# WQMS.net
KiCad netlist of a schematic drawn in EAGLE
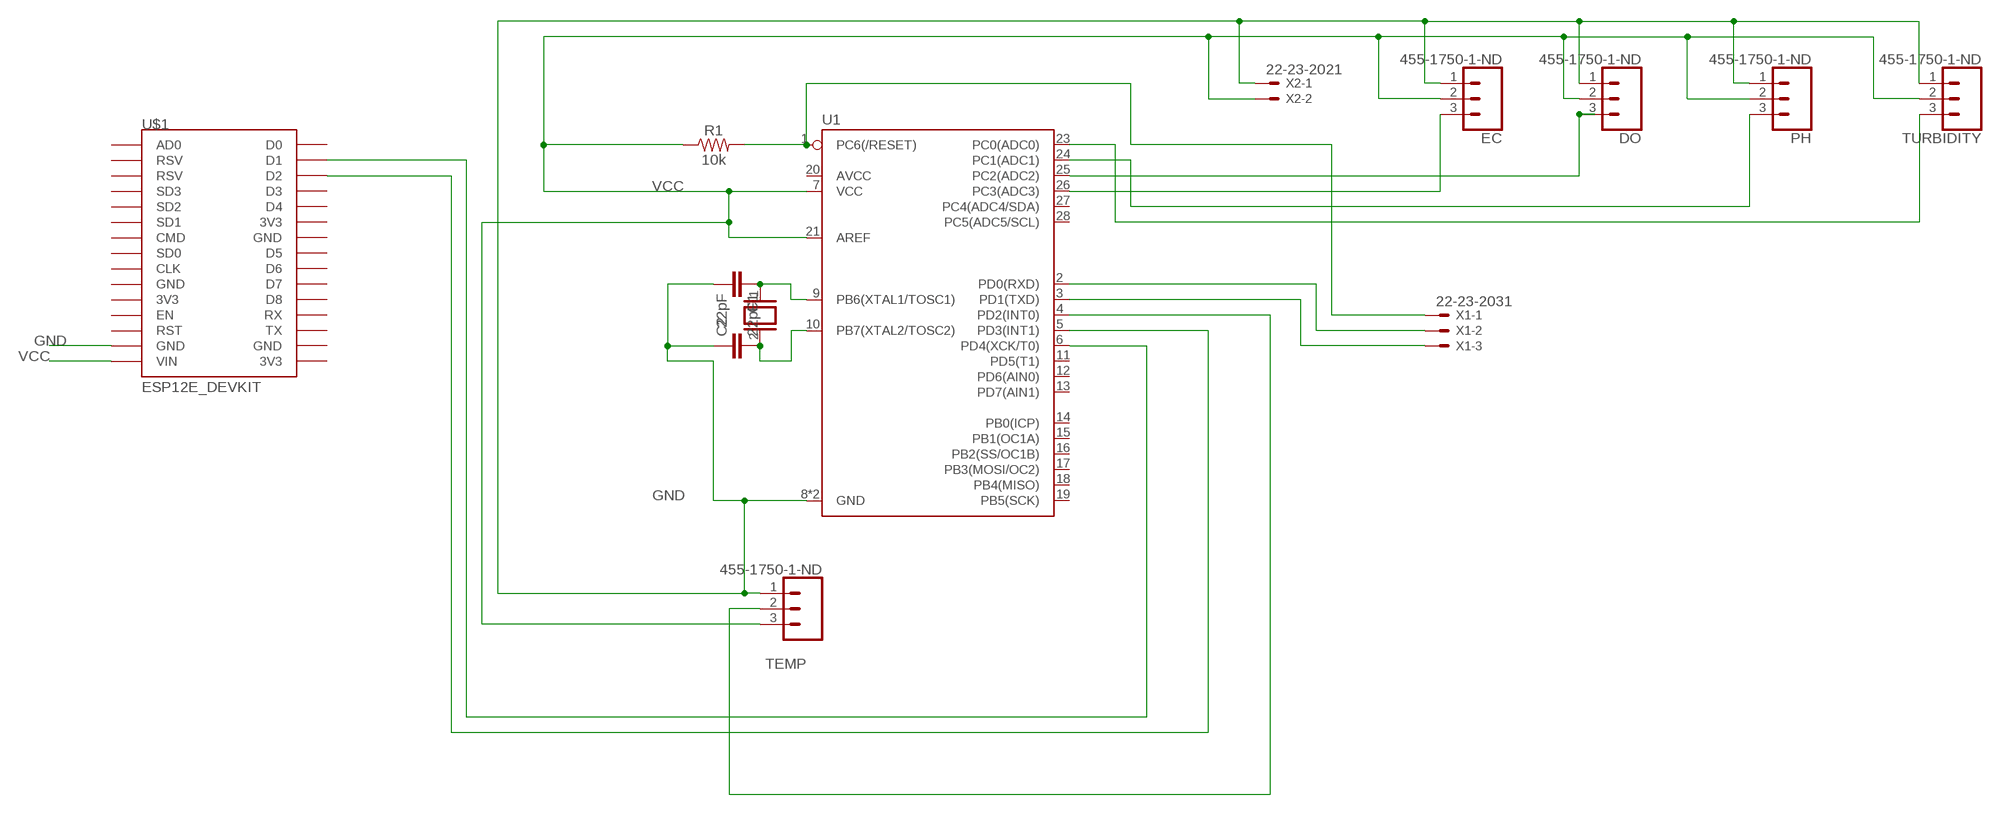
[diagram p0: schematic, sheet 1]

(export (version "E")
  (design (tool "Eeschema 10.0.6"))
  (components
    (comp (ref "C1")
      (value "22pF")
      (footprint "eagle-import:CAP-PTH-2.54")
      (libsource (lib "eagle-import") (part "22PF-PTH-2.54MM-200V-5%"))
    )
    (comp (ref "C2")
      (value "22pF")
      (footprint "eagle-import:CAP-PTH-2.54")
      (libsource (lib "eagle-import") (part "22PF-PTH-2.54MM-200V-5%"))
    )
    (comp (ref "DO")
      (value "455-1750-1-ND")
      (footprint "eagle-import:1X03")
      (libsource (lib "eagle-import") (part "CONN_03"))
    )
    (comp (ref "EC")
      (value "455-1750-1-ND")
      (footprint "eagle-import:1X03")
      (libsource (lib "eagle-import") (part "CONN_03"))
    )
    (comp (ref "PH")
      (value "455-1750-1-ND")
      (footprint "eagle-import:1X03")
      (libsource (lib "eagle-import") (part "CONN_03"))
    )
    (comp (ref "Q1")
      (value "XTAL")
      (footprint "eagle-import:Q")
      (libsource (lib "eagle-import") (part "XTAL"))
    )
    (comp (ref "R1")
      (value "10k")
      (footprint "eagle-import:AXIAL-0.3")
      (libsource (lib "eagle-import") (part "10KOHM-HORIZ-1/4W-1%"))
    )
    (comp (ref "TEMP")
      (value "455-1750-1-ND")
      (footprint "eagle-import:1X03")
      (libsource (lib "eagle-import") (part "CONN_03"))
    )
    (comp (ref "TURBIDITY")
      (value "455-1750-1-ND")
      (footprint "eagle-import:1X03")
      (libsource (lib "eagle-import") (part "CONN_03"))
    )
    (comp (ref "U$1")
      (value "ESP12E_DEVKIT")
      (footprint "eagle-import:ESP12E_DEVKIT")
      (libsource (lib "eagle-import") (part "ESP12E_DEVKIT"))
    )
    (comp (ref "U1")
      (value "328P")
      (footprint "eagle-import:DIP28")
      (libsource (lib "eagle-import") (part "ATMEGA328P_PDIP"))
    )
    (comp (ref "X1")
      (value "22-23-2031")
      (footprint "eagle-import:22-23-2031")
      (fields (field (name "MF") "MOLEX"))
      (libsource (lib "eagle-import") (part "22-23-2031"))
    )
    (comp (ref "X2")
      (value "22-23-2021")
      (footprint "eagle-import:22-23-2021")
      (fields (field (name "MF") "MOLEX"))
      (libsource (lib "eagle-import") (part "22-23-2021"))
    )
  )
  (nets
    (net (code "1") (name "/GND") (class "Default")
      (node (ref "C1") (pin "2") (pinfunction "2_2") (pintype "passive"))
      (node (ref "C2") (pin "1") (pinfunction "1_1") (pintype "passive"))
      (node (ref "DO") (pin "1") (pinfunction "1_1") (pintype "passive"))
      (node (ref "EC") (pin "1") (pinfunction "1_1") (pintype "passive"))
      (node (ref "PH") (pin "1") (pinfunction "1_1") (pintype "passive"))
      (node (ref "TEMP") (pin "1") (pinfunction "1_1") (pintype "passive"))
      (node (ref "TURBIDITY") (pin "1") (pinfunction "1_1") (pintype "passive"))
      (node (ref "U$1") (pin "GND@1") (pinfunction "GND_GND@1") (pintype "bidirectional"))
      (node (ref "U1") (pin "22") (pinfunction "GND_22") (pintype "bidirectional"))
      (node (ref "U1") (pin "8") (pinfunction "GND_8") (pintype "bidirectional"))
      (node (ref "X2") (pin "1") (pinfunction "S_1") (pintype "passive"))
    )
    (net (code "2") (name "/VCC") (class "Default")
      (node (ref "DO") (pin "2") (pinfunction "2_2") (pintype "passive"))
      (node (ref "EC") (pin "2") (pinfunction "2_2") (pintype "passive"))
      (node (ref "PH") (pin "2") (pinfunction "2_2") (pintype "passive"))
      (node (ref "R1") (pin "P$1") (pinfunction "1_P$1") (pintype "passive"))
      (node (ref "R1") (pin "P$2") (pinfunction "2_P$2") (pintype "passive"))
      (node (ref "TEMP") (pin "3") (pinfunction "3_3") (pintype "passive"))
      (node (ref "TURBIDITY") (pin "2") (pinfunction "2_2") (pintype "passive"))
      (node (ref "U$1") (pin "VIN") (pinfunction "VIN_VIN") (pintype "bidirectional"))
      (node (ref "U1") (pin "1") (pinfunction "PC6(/RESET)_1") (pintype "bidirectional"))
      (node (ref "U1") (pin "21") (pinfunction "AREF_21") (pintype "bidirectional"))
      (node (ref "U1") (pin "7") (pinfunction "VCC_7") (pintype "bidirectional"))
      (node (ref "X1") (pin "1") (pinfunction "S_1") (pintype "passive"))
      (node (ref "X2") (pin "2") (pinfunction "S_2") (pintype "passive"))
    )
    (net (code "3") (name "Net-(U1-PB6(XTAL1{slash}TOSC1))") (class "Default")
      (node (ref "C1") (pin "1") (pinfunction "1_1") (pintype "passive"))
      (node (ref "Q1") (pin "1") (pinfunction "1_1") (pintype "passive"))
      (node (ref "U1") (pin "9") (pinfunction "PB6(XTAL1/TOSC1)_9") (pintype "bidirectional"))
    )
    (net (code "4") (name "Net-(U1-PB7(XTAL2{slash}TOSC2))") (class "Default")
      (node (ref "C2") (pin "2") (pinfunction "2_2") (pintype "passive"))
      (node (ref "Q1") (pin "2") (pinfunction "2_2") (pintype "passive"))
      (node (ref "U1") (pin "10") (pinfunction "PB7(XTAL2/TOSC2)_10") (pintype "bidirectional"))
    )
    (net (code "5") (name "Net-(U1-PC0(ADC0))") (class "Default")
      (node (ref "TURBIDITY") (pin "3") (pinfunction "3_3") (pintype "passive"))
      (node (ref "U1") (pin "23") (pinfunction "PC0(ADC0)_23") (pintype "bidirectional"))
    )
    (net (code "6") (name "Net-(U1-PC1(ADC1))") (class "Default")
      (node (ref "PH") (pin "3") (pinfunction "3_3") (pintype "passive"))
      (node (ref "U1") (pin "24") (pinfunction "PC1(ADC1)_24") (pintype "bidirectional"))
    )
    (net (code "7") (name "Net-(U1-PC2(ADC2))") (class "Default")
      (node (ref "DO") (pin "3") (pinfunction "3_3") (pintype "passive"))
      (node (ref "U1") (pin "25") (pinfunction "PC2(ADC2)_25") (pintype "bidirectional"))
    )
    (net (code "8") (name "Net-(U1-PC3(ADC3))") (class "Default")
      (node (ref "EC") (pin "3") (pinfunction "3_3") (pintype "passive"))
      (node (ref "U1") (pin "26") (pinfunction "PC3(ADC3)_26") (pintype "bidirectional"))
    )
    (net (code "9") (name "Net-(U1-PD0(RXD))") (class "Default")
      (node (ref "U1") (pin "2") (pinfunction "PD0(RXD)_2") (pintype "bidirectional"))
      (node (ref "X1") (pin "2") (pinfunction "S_2") (pintype "passive"))
    )
    (net (code "10") (name "Net-(U1-PD1(TXD))") (class "Default")
      (node (ref "U1") (pin "3") (pinfunction "PD1(TXD)_3") (pintype "bidirectional"))
      (node (ref "X1") (pin "3") (pinfunction "S_3") (pintype "passive"))
    )
    (net (code "11") (name "Net-(U1-PD2(INT0))") (class "Default")
      (node (ref "TEMP") (pin "2") (pinfunction "2_2") (pintype "passive"))
      (node (ref "U1") (pin "4") (pinfunction "PD2(INT0)_4") (pintype "bidirectional"))
    )
    (net (code "12") (name "Net-(U1-PD3(INT1))") (class "Default")
      (node (ref "U$1") (pin "D2") (pinfunction "D2_D2") (pintype "bidirectional"))
      (node (ref "U1") (pin "5") (pinfunction "PD3(INT1)_5") (pintype "bidirectional"))
    )
    (net (code "13") (name "Net-(U1-PD4(XCK{slash}T0))") (class "Default")
      (node (ref "U$1") (pin "D1") (pinfunction "D1_D1") (pintype "bidirectional"))
      (node (ref "U1") (pin "6") (pinfunction "PD4(XCK/T0)_6") (pintype "bidirectional"))
    )
    (net (code "14") (name "unconnected-(U$1-3V3-Pad3V3@0)") (class "Default")
      (node (ref "U$1") (pin "3V3@0") (pinfunction "3V3_3V3@0") (pintype "bidirectional"))
    )
    (net (code "15") (name "unconnected-(U$1-3V3-Pad3V3@1)") (class "Default")
      (node (ref "U$1") (pin "3V3@1") (pinfunction "3V3_3V3@1") (pintype "bidirectional"))
    )
    (net (code "16") (name "unconnected-(U$1-3V3-Pad3V3@2)") (class "Default")
      (node (ref "U$1") (pin "3V3@2") (pinfunction "3V3_3V3@2") (pintype "bidirectional"))
    )
    (net (code "17") (name "unconnected-(U$1-GND-PadGND@0)") (class "Default")
      (node (ref "U$1") (pin "GND@0") (pinfunction "GND_GND@0") (pintype "bidirectional"))
    )
    (net (code "18") (name "unconnected-(U$1-GND-PadGND@2)") (class "Default")
      (node (ref "U$1") (pin "GND@2") (pinfunction "GND_GND@2") (pintype "bidirectional"))
    )
    (net (code "19") (name "unconnected-(U$1-GND-PadGND@3)") (class "Default")
      (node (ref "U$1") (pin "GND@3") (pinfunction "GND_GND@3") (pintype "bidirectional"))
    )
    (net (code "20") (name "unconnected-(U$1-PadAD0)") (class "Default")
      (node (ref "U$1") (pin "AD0") (pinfunction "AD0_AD0") (pintype "bidirectional"))
    )
    (net (code "21") (name "unconnected-(U$1-PadCLK)") (class "Default")
      (node (ref "U$1") (pin "CLK") (pinfunction "CLK_CLK") (pintype "bidirectional"))
    )
    (net (code "22") (name "unconnected-(U$1-PadCMD)") (class "Default")
      (node (ref "U$1") (pin "CMD") (pinfunction "CMD_CMD") (pintype "bidirectional"))
    )
    (net (code "23") (name "unconnected-(U$1-PadD0)") (class "Default")
      (node (ref "U$1") (pin "D0") (pinfunction "D0_D0") (pintype "bidirectional"))
    )
    (net (code "24") (name "unconnected-(U$1-PadD3)") (class "Default")
      (node (ref "U$1") (pin "D3") (pinfunction "D3_D3") (pintype "bidirectional"))
    )
    (net (code "25") (name "unconnected-(U$1-PadD4)") (class "Default")
      (node (ref "U$1") (pin "D4") (pinfunction "D4_D4") (pintype "bidirectional"))
    )
    (net (code "26") (name "unconnected-(U$1-PadD5)") (class "Default")
      (node (ref "U$1") (pin "D5") (pinfunction "D5_D5") (pintype "bidirectional"))
    )
    (net (code "27") (name "unconnected-(U$1-PadD6)") (class "Default")
      (node (ref "U$1") (pin "D6") (pinfunction "D6_D6") (pintype "bidirectional"))
    )
    (net (code "28") (name "unconnected-(U$1-PadD7)") (class "Default")
      (node (ref "U$1") (pin "D7") (pinfunction "D7_D7") (pintype "bidirectional"))
    )
    (net (code "29") (name "unconnected-(U$1-PadD8)") (class "Default")
      (node (ref "U$1") (pin "D8") (pinfunction "D8_D8") (pintype "bidirectional"))
    )
    (net (code "30") (name "unconnected-(U$1-PadEN)") (class "Default")
      (node (ref "U$1") (pin "EN") (pinfunction "EN_EN") (pintype "bidirectional"))
    )
    (net (code "31") (name "unconnected-(U$1-PadRST)") (class "Default")
      (node (ref "U$1") (pin "RST") (pinfunction "RST_RST") (pintype "bidirectional"))
    )
    (net (code "32") (name "unconnected-(U$1-PadRX)") (class "Default")
      (node (ref "U$1") (pin "RX") (pinfunction "RX_RX") (pintype "bidirectional"))
    )
    (net (code "33") (name "unconnected-(U$1-PadSD0)") (class "Default")
      (node (ref "U$1") (pin "SD0") (pinfunction "SD0_SD0") (pintype "bidirectional"))
    )
    (net (code "34") (name "unconnected-(U$1-PadSD1)") (class "Default")
      (node (ref "U$1") (pin "SD1") (pinfunction "SD1_SD1") (pintype "bidirectional"))
    )
    (net (code "35") (name "unconnected-(U$1-PadSD2)") (class "Default")
      (node (ref "U$1") (pin "SD2") (pinfunction "SD2_SD2") (pintype "bidirectional"))
    )
    (net (code "36") (name "unconnected-(U$1-PadSD3)") (class "Default")
      (node (ref "U$1") (pin "SD3") (pinfunction "SD3_SD3") (pintype "bidirectional"))
    )
    (net (code "37") (name "unconnected-(U$1-PadTX)") (class "Default")
      (node (ref "U$1") (pin "TX") (pinfunction "TX_TX") (pintype "bidirectional"))
    )
    (net (code "38") (name "unconnected-(U$1-RSV-PadRSV@0)") (class "Default")
      (node (ref "U$1") (pin "RSV@0") (pinfunction "RSV_RSV@0") (pintype "bidirectional"))
    )
    (net (code "39") (name "unconnected-(U$1-RSV-PadRSV@1)") (class "Default")
      (node (ref "U$1") (pin "RSV@1") (pinfunction "RSV_RSV@1") (pintype "bidirectional"))
    )
    (net (code "40") (name "unconnected-(U1-AVCC-Pad20)") (class "Default")
      (node (ref "U1") (pin "20") (pinfunction "AVCC_20") (pintype "bidirectional"))
    )
    (net (code "41") (name "unconnected-(U1-PB0(ICP)-Pad14)") (class "Default")
      (node (ref "U1") (pin "14") (pinfunction "PB0(ICP)_14") (pintype "bidirectional"))
    )
    (net (code "42") (name "unconnected-(U1-PB1(OC1A)-Pad15)") (class "Default")
      (node (ref "U1") (pin "15") (pinfunction "PB1(OC1A)_15") (pintype "bidirectional"))
    )
    (net (code "43") (name "unconnected-(U1-PB2(SS{slash}OC1B)-Pad16)") (class "Default")
      (node (ref "U1") (pin "16") (pinfunction "PB2(SS/OC1B)_16") (pintype "bidirectional"))
    )
    (net (code "44") (name "unconnected-(U1-PB3(MOSI{slash}OC2)-Pad17)") (class "Default")
      (node (ref "U1") (pin "17") (pinfunction "PB3(MOSI/OC2)_17") (pintype "bidirectional"))
    )
    (net (code "45") (name "unconnected-(U1-PB4(MISO)-Pad18)") (class "Default")
      (node (ref "U1") (pin "18") (pinfunction "PB4(MISO)_18") (pintype "bidirectional"))
    )
    (net (code "46") (name "unconnected-(U1-PB5(SCK)-Pad19)") (class "Default")
      (node (ref "U1") (pin "19") (pinfunction "PB5(SCK)_19") (pintype "bidirectional"))
    )
    (net (code "47") (name "unconnected-(U1-PC4(ADC4{slash}SDA)-Pad27)") (class "Default")
      (node (ref "U1") (pin "27") (pinfunction "PC4(ADC4/SDA)_27") (pintype "bidirectional"))
    )
    (net (code "48") (name "unconnected-(U1-PC5(ADC5{slash}SCL)-Pad28)") (class "Default")
      (node (ref "U1") (pin "28") (pinfunction "PC5(ADC5/SCL)_28") (pintype "bidirectional"))
    )
    (net (code "49") (name "unconnected-(U1-PD5(T1)-Pad11)") (class "Default")
      (node (ref "U1") (pin "11") (pinfunction "PD5(T1)_11") (pintype "bidirectional"))
    )
    (net (code "50") (name "unconnected-(U1-PD6(AIN0)-Pad12)") (class "Default")
      (node (ref "U1") (pin "12") (pinfunction "PD6(AIN0)_12") (pintype "bidirectional"))
    )
    (net (code "51") (name "unconnected-(U1-PD7(AIN1)-Pad13)") (class "Default")
      (node (ref "U1") (pin "13") (pinfunction "PD7(AIN1)_13") (pintype "bidirectional"))
    )
  )
)
